# W103X.net
KiCad netlist of a schematic drawn in EAGLE
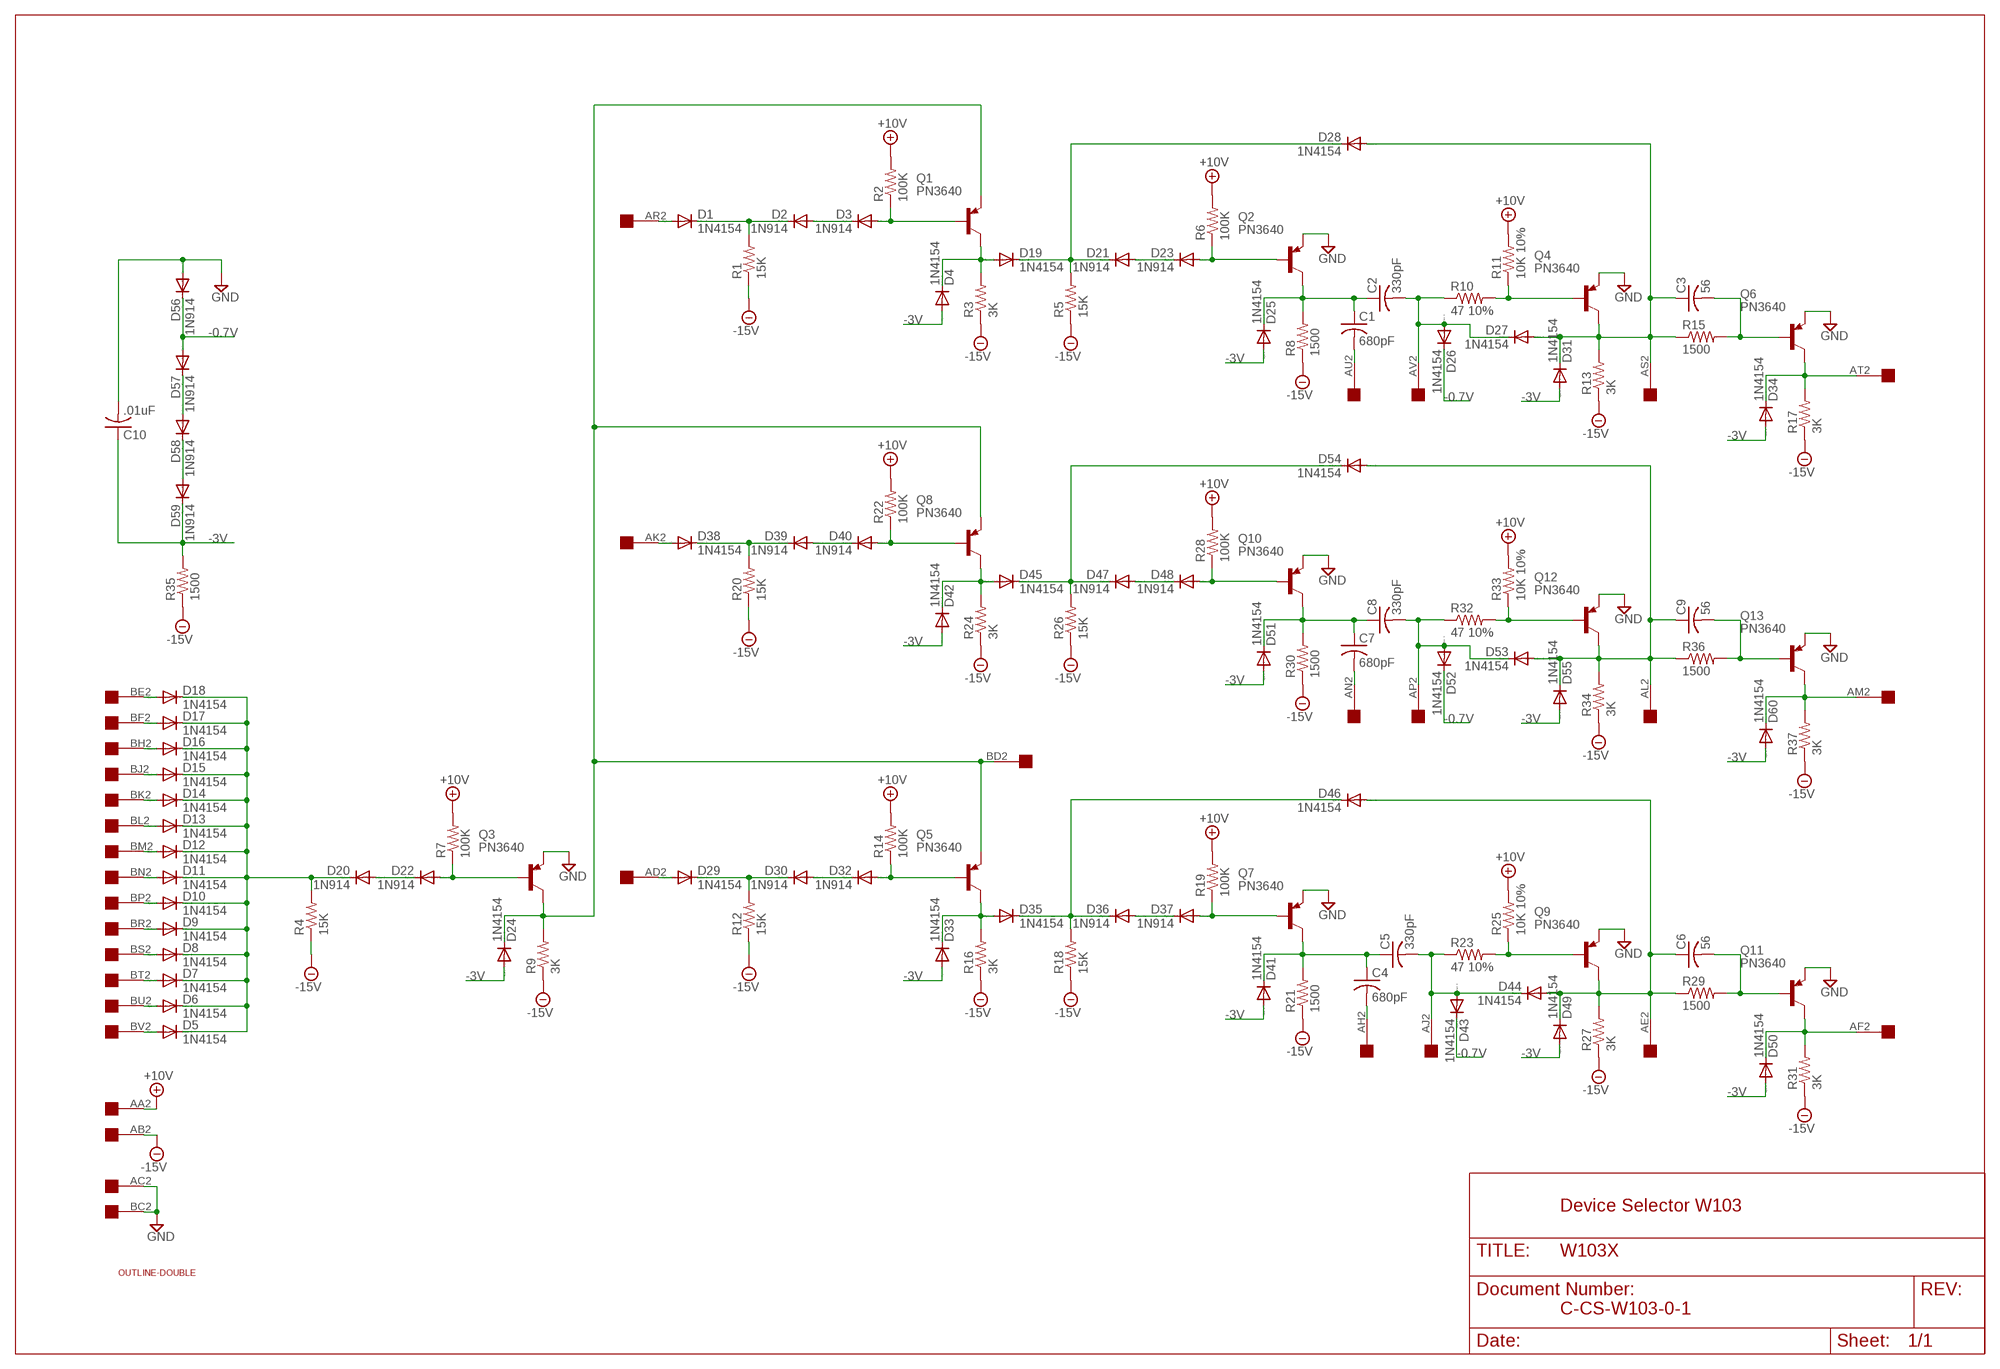
[diagram p0: schematic, sheet 1]

(export (version "E")
  (design (tool "Eeschema 10.0.6"))
  (components
    (comp (ref "C1")
      (value "680pF")
      (footprint "eagle-import:C075-032X103")
      (libsource (lib "eagle-import") (part "C-US075-032X103"))
    )
    (comp (ref "C2")
      (value "330pF")
      (footprint "eagle-import:C075-032X103")
      (libsource (lib "eagle-import") (part "C-US075-032X103"))
    )
    (comp (ref "C3")
      (value "56")
      (footprint "eagle-import:C075-032X103")
      (libsource (lib "eagle-import") (part "C-US075-032X103"))
    )
    (comp (ref "C4")
      (value "680pF")
      (footprint "eagle-import:C075-032X103")
      (libsource (lib "eagle-import") (part "C-US075-032X103"))
    )
    (comp (ref "C5")
      (value "330pF")
      (footprint "eagle-import:C075-032X103")
      (libsource (lib "eagle-import") (part "C-US075-032X103"))
    )
    (comp (ref "C6")
      (value "56")
      (footprint "eagle-import:C075-032X103")
      (libsource (lib "eagle-import") (part "C-US075-032X103"))
    )
    (comp (ref "C7")
      (value "680pF")
      (footprint "eagle-import:C075-032X103")
      (libsource (lib "eagle-import") (part "C-US075-032X103"))
    )
    (comp (ref "C8")
      (value "330pF")
      (footprint "eagle-import:C075-032X103")
      (libsource (lib "eagle-import") (part "C-US075-032X103"))
    )
    (comp (ref "C9")
      (value "56")
      (footprint "eagle-import:C075-032X103")
      (libsource (lib "eagle-import") (part "C-US075-032X103"))
    )
    (comp (ref "C10")
      (value ".01uF")
      (footprint "eagle-import:C075-032X103")
      (libsource (lib "eagle-import") (part "C-US075-032X103"))
    )
    (comp (ref "D1")
      (value "1N4154")
      (footprint "eagle-import:DO35-10")
      (libsource (lib "eagle-import") (part "1N4148DO35-10"))
    )
    (comp (ref "D2")
      (value "1N914")
      (footprint "eagle-import:DO35-10")
      (libsource (lib "eagle-import") (part "1N4148DO35-10"))
    )
    (comp (ref "D3")
      (value "1N914")
      (footprint "eagle-import:DO35-10")
      (libsource (lib "eagle-import") (part "1N4148DO35-10"))
    )
    (comp (ref "D4")
      (value "1N4154")
      (footprint "eagle-import:DO35-10")
      (libsource (lib "eagle-import") (part "1N4148DO35-10"))
    )
    (comp (ref "D5")
      (value "1N4154")
      (footprint "eagle-import:DO35-10")
      (libsource (lib "eagle-import") (part "1N4148DO35-10"))
    )
    (comp (ref "D6")
      (value "1N4154")
      (footprint "eagle-import:DO35-10")
      (libsource (lib "eagle-import") (part "1N4148DO35-10"))
    )
    (comp (ref "D7")
      (value "1N4154")
      (footprint "eagle-import:DO35-10")
      (libsource (lib "eagle-import") (part "1N4148DO35-10"))
    )
    (comp (ref "D8")
      (value "1N4154")
      (footprint "eagle-import:DO35-10")
      (libsource (lib "eagle-import") (part "1N4148DO35-10"))
    )
    (comp (ref "D9")
      (value "1N4154")
      (footprint "eagle-import:DO35-10")
      (libsource (lib "eagle-import") (part "1N4148DO35-10"))
    )
    (comp (ref "D10")
      (value "1N4154")
      (footprint "eagle-import:DO35-10")
      (libsource (lib "eagle-import") (part "1N4148DO35-10"))
    )
    (comp (ref "D11")
      (value "1N4154")
      (footprint "eagle-import:DO35-10")
      (libsource (lib "eagle-import") (part "1N4148DO35-10"))
    )
    (comp (ref "D12")
      (value "1N4154")
      (footprint "eagle-import:DO35-10")
      (libsource (lib "eagle-import") (part "1N4148DO35-10"))
    )
    (comp (ref "D13")
      (value "1N4154")
      (footprint "eagle-import:DO35-10")
      (libsource (lib "eagle-import") (part "1N4148DO35-10"))
    )
    (comp (ref "D14")
      (value "1N4154")
      (footprint "eagle-import:DO35-10")
      (libsource (lib "eagle-import") (part "1N4148DO35-10"))
    )
    (comp (ref "D15")
      (value "1N4154")
      (footprint "eagle-import:DO35-10")
      (libsource (lib "eagle-import") (part "1N4148DO35-10"))
    )
    (comp (ref "D16")
      (value "1N4154")
      (footprint "eagle-import:DO35-10")
      (libsource (lib "eagle-import") (part "1N4148DO35-10"))
    )
    (comp (ref "D17")
      (value "1N4154")
      (footprint "eagle-import:DO35-10")
      (libsource (lib "eagle-import") (part "1N4148DO35-10"))
    )
    (comp (ref "D18")
      (value "1N4154")
      (footprint "eagle-import:DO35-10")
      (libsource (lib "eagle-import") (part "1N4148DO35-10"))
    )
    (comp (ref "D19")
      (value "1N4154")
      (footprint "eagle-import:DO35-10")
      (libsource (lib "eagle-import") (part "1N4148DO35-10"))
    )
    (comp (ref "D20")
      (value "1N914")
      (footprint "eagle-import:DO35-10")
      (libsource (lib "eagle-import") (part "1N4148DO35-10"))
    )
    (comp (ref "D21")
      (value "1N914")
      (footprint "eagle-import:DO35-10")
      (libsource (lib "eagle-import") (part "1N4148DO35-10"))
    )
    (comp (ref "D22")
      (value "1N914")
      (footprint "eagle-import:DO35-10")
      (libsource (lib "eagle-import") (part "1N4148DO35-10"))
    )
    (comp (ref "D23")
      (value "1N914")
      (footprint "eagle-import:DO35-10")
      (libsource (lib "eagle-import") (part "1N4148DO35-10"))
    )
    (comp (ref "D24")
      (value "1N4154")
      (footprint "eagle-import:DO35-10")
      (libsource (lib "eagle-import") (part "1N4148DO35-10"))
    )
    (comp (ref "D25")
      (value "1N4154")
      (footprint "eagle-import:DO35-10")
      (libsource (lib "eagle-import") (part "1N4148DO35-10"))
    )
    (comp (ref "D26")
      (value "1N4154")
      (footprint "eagle-import:DO35-10")
      (libsource (lib "eagle-import") (part "1N4148DO35-10"))
    )
    (comp (ref "D27")
      (value "1N4154")
      (footprint "eagle-import:DO35-10")
      (libsource (lib "eagle-import") (part "1N4148DO35-10"))
    )
    (comp (ref "D28")
      (value "1N4154")
      (footprint "eagle-import:DO35-10")
      (libsource (lib "eagle-import") (part "1N4148DO35-10"))
    )
    (comp (ref "D29")
      (value "1N4154")
      (footprint "eagle-import:DO35-10")
      (libsource (lib "eagle-import") (part "1N4148DO35-10"))
    )
    (comp (ref "D30")
      (value "1N914")
      (footprint "eagle-import:DO35-10")
      (libsource (lib "eagle-import") (part "1N4148DO35-10"))
    )
    (comp (ref "D31")
      (value "1N4154")
      (footprint "eagle-import:DO35-10")
      (libsource (lib "eagle-import") (part "1N4148DO35-10"))
    )
    (comp (ref "D32")
      (value "1N914")
      (footprint "eagle-import:DO35-10")
      (libsource (lib "eagle-import") (part "1N4148DO35-10"))
    )
    (comp (ref "D33")
      (value "1N4154")
      (footprint "eagle-import:DO35-10")
      (libsource (lib "eagle-import") (part "1N4148DO35-10"))
    )
    (comp (ref "D34")
      (value "1N4154")
      (footprint "eagle-import:DO35-10")
      (libsource (lib "eagle-import") (part "1N4148DO35-10"))
    )
    (comp (ref "D35")
      (value "1N4154")
      (footprint "eagle-import:DO35-10")
      (libsource (lib "eagle-import") (part "1N4148DO35-10"))
    )
    (comp (ref "D36")
      (value "1N914")
      (footprint "eagle-import:DO35-10")
      (libsource (lib "eagle-import") (part "1N4148DO35-10"))
    )
    (comp (ref "D37")
      (value "1N914")
      (footprint "eagle-import:DO35-10")
      (libsource (lib "eagle-import") (part "1N4148DO35-10"))
    )
    (comp (ref "D38")
      (value "1N4154")
      (footprint "eagle-import:DO35-10")
      (libsource (lib "eagle-import") (part "1N4148DO35-10"))
    )
    (comp (ref "D39")
      (value "1N914")
      (footprint "eagle-import:DO35-10")
      (libsource (lib "eagle-import") (part "1N4148DO35-10"))
    )
    (comp (ref "D40")
      (value "1N914")
      (footprint "eagle-import:DO35-10")
      (libsource (lib "eagle-import") (part "1N4148DO35-10"))
    )
    (comp (ref "D41")
      (value "1N4154")
      (footprint "eagle-import:DO35-10")
      (libsource (lib "eagle-import") (part "1N4148DO35-10"))
    )
    (comp (ref "D42")
      (value "1N4154")
      (footprint "eagle-import:DO35-10")
      (libsource (lib "eagle-import") (part "1N4148DO35-10"))
    )
    (comp (ref "D43")
      (value "1N4154")
      (footprint "eagle-import:DO35-10")
      (libsource (lib "eagle-import") (part "1N4148DO35-10"))
    )
    (comp (ref "D44")
      (value "1N4154")
      (footprint "eagle-import:DO35-10")
      (libsource (lib "eagle-import") (part "1N4148DO35-10"))
    )
    (comp (ref "D45")
      (value "1N4154")
      (footprint "eagle-import:DO35-10")
      (libsource (lib "eagle-import") (part "1N4148DO35-10"))
    )
    (comp (ref "D46")
      (value "1N4154")
      (footprint "eagle-import:DO35-10")
      (libsource (lib "eagle-import") (part "1N4148DO35-10"))
    )
    (comp (ref "D47")
      (value "1N914")
      (footprint "eagle-import:DO35-10")
      (libsource (lib "eagle-import") (part "1N4148DO35-10"))
    )
    (comp (ref "D48")
      (value "1N914")
      (footprint "eagle-import:DO35-10")
      (libsource (lib "eagle-import") (part "1N4148DO35-10"))
    )
    (comp (ref "D49")
      (value "1N4154")
      (footprint "eagle-import:DO35-10")
      (libsource (lib "eagle-import") (part "1N4148DO35-10"))
    )
    (comp (ref "D50")
      (value "1N4154")
      (footprint "eagle-import:DO35-10")
      (libsource (lib "eagle-import") (part "1N4148DO35-10"))
    )
    (comp (ref "D51")
      (value "1N4154")
      (footprint "eagle-import:DO35-10")
      (libsource (lib "eagle-import") (part "1N4148DO35-10"))
    )
    (comp (ref "D52")
      (value "1N4154")
      (footprint "eagle-import:DO35-10")
      (libsource (lib "eagle-import") (part "1N4148DO35-10"))
    )
    (comp (ref "D53")
      (value "1N4154")
      (footprint "eagle-import:DO35-10")
      (libsource (lib "eagle-import") (part "1N4148DO35-10"))
    )
    (comp (ref "D54")
      (value "1N4154")
      (footprint "eagle-import:DO35-10")
      (libsource (lib "eagle-import") (part "1N4148DO35-10"))
    )
    (comp (ref "D55")
      (value "1N4154")
      (footprint "eagle-import:DO35-10")
      (libsource (lib "eagle-import") (part "1N4148DO35-10"))
    )
    (comp (ref "D56")
      (value "1N914")
      (footprint "eagle-import:DO35-10")
      (libsource (lib "eagle-import") (part "1N4148DO35-10"))
    )
    (comp (ref "D57")
      (value "1N914")
      (footprint "eagle-import:DO35-10")
      (libsource (lib "eagle-import") (part "1N4148DO35-10"))
    )
    (comp (ref "D58")
      (value "1N914")
      (footprint "eagle-import:DO35-10")
      (libsource (lib "eagle-import") (part "1N4148DO35-10"))
    )
    (comp (ref "D59")
      (value "1N914")
      (footprint "eagle-import:DO35-10")
      (libsource (lib "eagle-import") (part "1N4148DO35-10"))
    )
    (comp (ref "D60")
      (value "1N4154")
      (footprint "eagle-import:DO35-10")
      (libsource (lib "eagle-import") (part "1N4148DO35-10"))
    )
    (comp (ref "Q1")
      (value "PN3640")
      (footprint "eagle-import:TO39")
      (libsource (lib "eagle-import") (part "2N2904"))
    )
    (comp (ref "Q2")
      (value "PN3640")
      (footprint "eagle-import:TO39")
      (libsource (lib "eagle-import") (part "2N2904"))
    )
    (comp (ref "Q3")
      (value "PN3640")
      (footprint "eagle-import:TO39")
      (libsource (lib "eagle-import") (part "2N2904"))
    )
    (comp (ref "Q4")
      (value "PN3640")
      (footprint "eagle-import:TO39")
      (libsource (lib "eagle-import") (part "2N2904"))
    )
    (comp (ref "Q5")
      (value "PN3640")
      (footprint "eagle-import:TO39")
      (libsource (lib "eagle-import") (part "2N2904"))
    )
    (comp (ref "Q6")
      (value "PN3640")
      (footprint "eagle-import:TO39")
      (libsource (lib "eagle-import") (part "2N2904"))
    )
    (comp (ref "Q7")
      (value "PN3640")
      (footprint "eagle-import:TO39")
      (libsource (lib "eagle-import") (part "2N2904"))
    )
    (comp (ref "Q8")
      (value "PN3640")
      (footprint "eagle-import:TO39")
      (libsource (lib "eagle-import") (part "2N2904"))
    )
    (comp (ref "Q9")
      (value "PN3640")
      (footprint "eagle-import:TO39")
      (libsource (lib "eagle-import") (part "2N2904"))
    )
    (comp (ref "Q10")
      (value "PN3640")
      (footprint "eagle-import:TO39")
      (libsource (lib "eagle-import") (part "2N2904"))
    )
    (comp (ref "Q11")
      (value "PN3640")
      (footprint "eagle-import:TO39")
      (libsource (lib "eagle-import") (part "2N2904"))
    )
    (comp (ref "Q12")
      (value "PN3640")
      (footprint "eagle-import:TO39")
      (libsource (lib "eagle-import") (part "2N2904"))
    )
    (comp (ref "Q13")
      (value "PN3640")
      (footprint "eagle-import:TO39")
      (libsource (lib "eagle-import") (part "2N2904"))
    )
    (comp (ref "R1")
      (value "15K")
      (footprint "eagle-import:0207_10")
      (libsource (lib "eagle-import") (part "R-US_0207/10"))
    )
    (comp (ref "R2")
      (value "100K")
      (footprint "eagle-import:0207_10")
      (libsource (lib "eagle-import") (part "R-US_0207/10"))
    )
    (comp (ref "R3")
      (value "3K")
      (footprint "eagle-import:0207_10")
      (libsource (lib "eagle-import") (part "R-US_0207/10"))
    )
    (comp (ref "R4")
      (value "15K")
      (footprint "eagle-import:0207_10")
      (libsource (lib "eagle-import") (part "R-US_0207/10"))
    )
    (comp (ref "R5")
      (value "15K")
      (footprint "eagle-import:0207_10")
      (libsource (lib "eagle-import") (part "R-US_0207/10"))
    )
    (comp (ref "R6")
      (value "100K")
      (footprint "eagle-import:0207_10")
      (libsource (lib "eagle-import") (part "R-US_0207/10"))
    )
    (comp (ref "R7")
      (value "100K")
      (footprint "eagle-import:0207_10")
      (libsource (lib "eagle-import") (part "R-US_0207/10"))
    )
    (comp (ref "R8")
      (value "1500")
      (footprint "eagle-import:0207_10")
      (libsource (lib "eagle-import") (part "R-US_0207/10"))
    )
    (comp (ref "R9")
      (value "3K")
      (footprint "eagle-import:0207_10")
      (libsource (lib "eagle-import") (part "R-US_0207/10"))
    )
    (comp (ref "R10")
      (value "47 10%")
      (footprint "eagle-import:0207_10")
      (libsource (lib "eagle-import") (part "R-US_0207/10"))
    )
    (comp (ref "R11")
      (value "10K 10%")
      (footprint "eagle-import:0207_10")
      (libsource (lib "eagle-import") (part "R-US_0207/10"))
    )
    (comp (ref "R12")
      (value "15K")
      (footprint "eagle-import:0207_10")
      (libsource (lib "eagle-import") (part "R-US_0207/10"))
    )
    (comp (ref "R13")
      (value "3K")
      (footprint "eagle-import:0207_10")
      (libsource (lib "eagle-import") (part "R-US_0207/10"))
    )
    (comp (ref "R14")
      (value "100K")
      (footprint "eagle-import:0207_10")
      (libsource (lib "eagle-import") (part "R-US_0207/10"))
    )
    (comp (ref "R15")
      (value "1500")
      (footprint "eagle-import:0207_10")
      (libsource (lib "eagle-import") (part "R-US_0207/10"))
    )
    (comp (ref "R16")
      (value "3K")
      (footprint "eagle-import:0207_10")
      (libsource (lib "eagle-import") (part "R-US_0207/10"))
    )
    (comp (ref "R17")
      (value "3K")
      (footprint "eagle-import:0207_10")
      (libsource (lib "eagle-import") (part "R-US_0207/10"))
    )
    (comp (ref "R18")
      (value "15K")
      (footprint "eagle-import:0207_10")
      (libsource (lib "eagle-import") (part "R-US_0207/10"))
    )
    (comp (ref "R19")
      (value "100K")
      (footprint "eagle-import:0207_10")
      (libsource (lib "eagle-import") (part "R-US_0207/10"))
    )
    (comp (ref "R20")
      (value "15K")
      (footprint "eagle-import:0207_10")
      (libsource (lib "eagle-import") (part "R-US_0207/10"))
    )
    (comp (ref "R21")
      (value "1500")
      (footprint "eagle-import:0207_10")
      (libsource (lib "eagle-import") (part "R-US_0207/10"))
    )
    (comp (ref "R22")
      (value "100K")
      (footprint "eagle-import:0207_10")
      (libsource (lib "eagle-import") (part "R-US_0207/10"))
    )
    (comp (ref "R23")
      (value "47 10%")
      (footprint "eagle-import:0207_10")
      (libsource (lib "eagle-import") (part "R-US_0207/10"))
    )
    (comp (ref "R24")
      (value "3K")
      (footprint "eagle-import:0207_10")
      (libsource (lib "eagle-import") (part "R-US_0207/10"))
    )
    (comp (ref "R25")
      (value "10K 10%")
      (footprint "eagle-import:0207_10")
      (libsource (lib "eagle-import") (part "R-US_0207/10"))
    )
    (comp (ref "R26")
      (value "15K")
      (footprint "eagle-import:0207_10")
      (libsource (lib "eagle-import") (part "R-US_0207/10"))
    )
    (comp (ref "R27")
      (value "3K")
      (footprint "eagle-import:0207_10")
      (libsource (lib "eagle-import") (part "R-US_0207/10"))
    )
    (comp (ref "R28")
      (value "100K")
      (footprint "eagle-import:0207_10")
      (libsource (lib "eagle-import") (part "R-US_0207/10"))
    )
    (comp (ref "R29")
      (value "1500")
      (footprint "eagle-import:0207_10")
      (libsource (lib "eagle-import") (part "R-US_0207/10"))
    )
    (comp (ref "R30")
      (value "1500")
      (footprint "eagle-import:0207_10")
      (libsource (lib "eagle-import") (part "R-US_0207/10"))
    )
    (comp (ref "R31")
      (value "3K")
      (footprint "eagle-import:0207_10")
      (libsource (lib "eagle-import") (part "R-US_0207/10"))
    )
    (comp (ref "R32")
      (value "47 10%")
      (footprint "eagle-import:0207_10")
      (libsource (lib "eagle-import") (part "R-US_0207/10"))
    )
    (comp (ref "R33")
      (value "10K 10%")
      (footprint "eagle-import:0207_10")
      (libsource (lib "eagle-import") (part "R-US_0207/10"))
    )
    (comp (ref "R34")
      (value "3K")
      (footprint "eagle-import:0207_10")
      (libsource (lib "eagle-import") (part "R-US_0207/10"))
    )
    (comp (ref "R35")
      (value "1500")
      (footprint "eagle-import:0207_10")
      (libsource (lib "eagle-import") (part "R-US_0207/10"))
    )
    (comp (ref "R36")
      (value "1500")
      (footprint "eagle-import:0207_10")
      (libsource (lib "eagle-import") (part "R-US_0207/10"))
    )
    (comp (ref "R37")
      (value "3K")
      (footprint "eagle-import:0207_10")
      (libsource (lib "eagle-import") (part "R-US_0207/10"))
    )
    (comp (ref "U$1")
      (value "OUTLINE-DOUBLE")
      (footprint "eagle-import:DOUBLE")
      (libsource (lib "eagle-import") (part "OUTLINE-DOUBLE"))
    )
    (comp (ref "U$2")
      (value "DOUBLE")
      (footprint "eagle-import:EDGE-CON4")
      (libsource (lib "eagle-import") (part "DOUBLE"))
    )
  )
  (nets
    (net (code "1") (name "+10V") (class "Default")
      (node (ref "R11") (pin "2") (pinfunction "2_2") (pintype "passive"))
      (node (ref "R14") (pin "2") (pinfunction "2_2") (pintype "passive"))
      (node (ref "R19") (pin "2") (pinfunction "2_2") (pintype "passive"))
      (node (ref "R2") (pin "2") (pinfunction "2_2") (pintype "passive"))
      (node (ref "R22") (pin "2") (pinfunction "2_2") (pintype "passive"))
      (node (ref "R25") (pin "2") (pinfunction "2_2") (pintype "passive"))
      (node (ref "R28") (pin "2") (pinfunction "2_2") (pintype "passive"))
      (node (ref "R33") (pin "2") (pinfunction "2_2") (pintype "passive"))
      (node (ref "R6") (pin "2") (pinfunction "2_2") (pintype "passive"))
      (node (ref "R7") (pin "2") (pinfunction "2_2") (pintype "passive"))
      (node (ref "U$2") (pin "AA2") (pinfunction "1_AA2") (pintype "bidirectional"))
    )
    (net (code "2") (name "-15V") (class "Default")
      (node (ref "R1") (pin "1") (pinfunction "1_1") (pintype "passive"))
      (node (ref "R12") (pin "1") (pinfunction "1_1") (pintype "passive"))
      (node (ref "R13") (pin "1") (pinfunction "1_1") (pintype "passive"))
      (node (ref "R16") (pin "1") (pinfunction "1_1") (pintype "passive"))
      (node (ref "R17") (pin "1") (pinfunction "1_1") (pintype "passive"))
      (node (ref "R18") (pin "1") (pinfunction "1_1") (pintype "passive"))
      (node (ref "R20") (pin "1") (pinfunction "1_1") (pintype "passive"))
      (node (ref "R21") (pin "1") (pinfunction "1_1") (pintype "passive"))
      (node (ref "R24") (pin "1") (pinfunction "1_1") (pintype "passive"))
      (node (ref "R26") (pin "1") (pinfunction "1_1") (pintype "passive"))
      (node (ref "R27") (pin "1") (pinfunction "1_1") (pintype "passive"))
      (node (ref "R3") (pin "1") (pinfunction "1_1") (pintype "passive"))
      (node (ref "R30") (pin "1") (pinfunction "1_1") (pintype "passive"))
      (node (ref "R31") (pin "1") (pinfunction "1_1") (pintype "passive"))
      (node (ref "R34") (pin "1") (pinfunction "1_1") (pintype "passive"))
      (node (ref "R35") (pin "1") (pinfunction "1_1") (pintype "passive"))
      (node (ref "R37") (pin "1") (pinfunction "1_1") (pintype "passive"))
      (node (ref "R4") (pin "1") (pinfunction "1_1") (pintype "passive"))
      (node (ref "R5") (pin "1") (pinfunction "1_1") (pintype "passive"))
      (node (ref "R8") (pin "1") (pinfunction "1_1") (pintype "passive"))
      (node (ref "R9") (pin "1") (pinfunction "1_1") (pintype "passive"))
      (node (ref "U$2") (pin "AB2") (pinfunction "1_AB2") (pintype "bidirectional"))
    )
    (net (code "3") (name "/-0.7V") (class "Default")
      (node (ref "D26") (pin "C") (pinfunction "C_C") (pintype "passive"))
      (node (ref "D43") (pin "C") (pinfunction "C_C") (pintype "passive"))
      (node (ref "D52") (pin "C") (pinfunction "C_C") (pintype "passive"))
      (node (ref "D56") (pin "C") (pinfunction "C_C") (pintype "passive"))
      (node (ref "D57") (pin "A") (pinfunction "A_A") (pintype "passive"))
    )
    (net (code "4") (name "/-3V") (class "Default")
      (node (ref "C10") (pin "1") (pinfunction "1_1") (pintype "passive"))
      (node (ref "D24") (pin "A") (pinfunction "A_A") (pintype "passive"))
      (node (ref "D25") (pin "A") (pinfunction "A_A") (pintype "passive"))
      (node (ref "D31") (pin "A") (pinfunction "A_A") (pintype "passive"))
      (node (ref "D33") (pin "A") (pinfunction "A_A") (pintype "passive"))
      (node (ref "D34") (pin "A") (pinfunction "A_A") (pintype "passive"))
      (node (ref "D4") (pin "A") (pinfunction "A_A") (pintype "passive"))
      (node (ref "D41") (pin "A") (pinfunction "A_A") (pintype "passive"))
      (node (ref "D42") (pin "A") (pinfunction "A_A") (pintype "passive"))
      (node (ref "D49") (pin "A") (pinfunction "A_A") (pintype "passive"))
      (node (ref "D50") (pin "A") (pinfunction "A_A") (pintype "passive"))
      (node (ref "D51") (pin "A") (pinfunction "A_A") (pintype "passive"))
      (node (ref "D55") (pin "A") (pinfunction "A_A") (pintype "passive"))
      (node (ref "D59") (pin "C") (pinfunction "C_C") (pintype "passive"))
      (node (ref "D60") (pin "A") (pinfunction "A_A") (pintype "passive"))
      (node (ref "R35") (pin "2") (pinfunction "2_2") (pintype "passive"))
    )
    (net (code "5") (name "GND") (class "Default")
      (node (ref "C10") (pin "2") (pinfunction "2_2") (pintype "passive"))
      (node (ref "D56") (pin "A") (pinfunction "A_A") (pintype "passive"))
      (node (ref "Q10") (pin "1") (pinfunction "E_1") (pintype "passive"))
      (node (ref "Q11") (pin "1") (pinfunction "E_1") (pintype "passive"))
      (node (ref "Q12") (pin "1") (pinfunction "E_1") (pintype "passive"))
      (node (ref "Q13") (pin "1") (pinfunction "E_1") (pintype "passive"))
      (node (ref "Q2") (pin "1") (pinfunction "E_1") (pintype "passive"))
      (node (ref "Q3") (pin "1") (pinfunction "E_1") (pintype "passive"))
      (node (ref "Q4") (pin "1") (pinfunction "E_1") (pintype "passive"))
      (node (ref "Q6") (pin "1") (pinfunction "E_1") (pintype "passive"))
      (node (ref "Q7") (pin "1") (pinfunction "E_1") (pintype "passive"))
      (node (ref "Q9") (pin "1") (pinfunction "E_1") (pintype "passive"))
      (node (ref "U$2") (pin "AC2") (pinfunction "1_AC2") (pintype "bidirectional"))
      (node (ref "U$2") (pin "BC2") (pinfunction "1_BC2") (pintype "bidirectional"))
    )
    (net (code "6") (name "Net-(D1-PadC)") (class "Default")
      (node (ref "D1") (pin "C") (pinfunction "C_C") (pintype "passive"))
      (node (ref "D2") (pin "C") (pinfunction "C_C") (pintype "passive"))
      (node (ref "R1") (pin "2") (pinfunction "2_2") (pintype "passive"))
    )
    (net (code "7") (name "Net-(D2-PadA)") (class "Default")
      (node (ref "D2") (pin "A") (pinfunction "A_A") (pintype "passive"))
      (node (ref "D3") (pin "C") (pinfunction "C_C") (pintype "passive"))
    )
    (net (code "8") (name "Net-(D10-PadC)") (class "Default")
      (node (ref "D10") (pin "C") (pinfunction "C_C") (pintype "passive"))
      (node (ref "D11") (pin "C") (pinfunction "C_C") (pintype "passive"))
      (node (ref "D12") (pin "C") (pinfunction "C_C") (pintype "passive"))
      (node (ref "D13") (pin "C") (pinfunction "C_C") (pintype "passive"))
      (node (ref "D14") (pin "C") (pinfunction "C_C") (pintype "passive"))
      (node (ref "D15") (pin "C") (pinfunction "C_C") (pintype "passive"))
      (node (ref "D16") (pin "C") (pinfunction "C_C") (pintype "passive"))
      (node (ref "D17") (pin "C") (pinfunction "C_C") (pintype "passive"))
      (node (ref "D18") (pin "C") (pinfunction "C_C") (pintype "passive"))
      (node (ref "D20") (pin "C") (pinfunction "C_C") (pintype "passive"))
      (node (ref "D5") (pin "C") (pinfunction "C_C") (pintype "passive"))
      (node (ref "D6") (pin "C") (pinfunction "C_C") (pintype "passive"))
      (node (ref "D7") (pin "C") (pinfunction "C_C") (pintype "passive"))
      (node (ref "D8") (pin "C") (pinfunction "C_C") (pintype "passive"))
      (node (ref "D9") (pin "C") (pinfunction "C_C") (pintype "passive"))
      (node (ref "R4") (pin "2") (pinfunction "2_2") (pintype "passive"))
    )
    (net (code "9") (name "Net-(D19-PadC)") (class "Default")
      (node (ref "D19") (pin "C") (pinfunction "C_C") (pintype "passive"))
      (node (ref "D21") (pin "C") (pinfunction "C_C") (pintype "passive"))
      (node (ref "D28") (pin "C") (pinfunction "C_C") (pintype "passive"))
      (node (ref "R5") (pin "2") (pinfunction "2_2") (pintype "passive"))
    )
    (net (code "10") (name "Net-(D20-PadA)") (class "Default")
      (node (ref "D20") (pin "A") (pinfunction "A_A") (pintype "passive"))
      (node (ref "D22") (pin "C") (pinfunction "C_C") (pintype "passive"))
    )
    (net (code "11") (name "Net-(D21-PadA)") (class "Default")
      (node (ref "D21") (pin "A") (pinfunction "A_A") (pintype "passive"))
      (node (ref "D23") (pin "C") (pinfunction "C_C") (pintype "passive"))
    )
    (net (code "12") (name "Net-(D29-PadC)") (class "Default")
      (node (ref "D29") (pin "C") (pinfunction "C_C") (pintype "passive"))
      (node (ref "D30") (pin "C") (pinfunction "C_C") (pintype "passive"))
      (node (ref "R12") (pin "2") (pinfunction "2_2") (pintype "passive"))
    )
    (net (code "13") (name "Net-(D30-PadA)") (class "Default")
      (node (ref "D30") (pin "A") (pinfunction "A_A") (pintype "passive"))
      (node (ref "D32") (pin "C") (pinfunction "C_C") (pintype "passive"))
    )
    (net (code "14") (name "Net-(D35-PadC)") (class "Default")
      (node (ref "D35") (pin "C") (pinfunction "C_C") (pintype "passive"))
      (node (ref "D36") (pin "C") (pinfunction "C_C") (pintype "passive"))
      (node (ref "D46") (pin "C") (pinfunction "C_C") (pintype "passive"))
      (node (ref "R18") (pin "2") (pinfunction "2_2") (pintype "passive"))
    )
    (net (code "15") (name "Net-(D36-PadA)") (class "Default")
      (node (ref "D36") (pin "A") (pinfunction "A_A") (pintype "passive"))
      (node (ref "D37") (pin "C") (pinfunction "C_C") (pintype "passive"))
    )
    (net (code "16") (name "Net-(D38-PadC)") (class "Default")
      (node (ref "D38") (pin "C") (pinfunction "C_C") (pintype "passive"))
      (node (ref "D39") (pin "C") (pinfunction "C_C") (pintype "passive"))
      (node (ref "R20") (pin "2") (pinfunction "2_2") (pintype "passive"))
    )
    (net (code "17") (name "Net-(D39-PadA)") (class "Default")
      (node (ref "D39") (pin "A") (pinfunction "A_A") (pintype "passive"))
      (node (ref "D40") (pin "C") (pinfunction "C_C") (pintype "passive"))
    )
    (net (code "18") (name "Net-(D45-PadC)") (class "Default")
      (node (ref "D45") (pin "C") (pinfunction "C_C") (pintype "passive"))
      (node (ref "D47") (pin "C") (pinfunction "C_C") (pintype "passive"))
      (node (ref "D54") (pin "C") (pinfunction "C_C") (pintype "passive"))
      (node (ref "R26") (pin "2") (pinfunction "2_2") (pintype "passive"))
    )
    (net (code "19") (name "Net-(D47-PadA)") (class "Default")
      (node (ref "D47") (pin "A") (pinfunction "A_A") (pintype "passive"))
      (node (ref "D48") (pin "C") (pinfunction "C_C") (pintype "passive"))
    )
    (net (code "20") (name "Net-(D57-PadC)") (class "Default")
      (node (ref "D57") (pin "C") (pinfunction "C_C") (pintype "passive"))
      (node (ref "D58") (pin "A") (pinfunction "A_A") (pintype "passive"))
    )
    (net (code "21") (name "Net-(D58-PadC)") (class "Default")
      (node (ref "D58") (pin "C") (pinfunction "C_C") (pintype "passive"))
      (node (ref "D59") (pin "A") (pinfunction "A_A") (pintype "passive"))
    )
    (net (code "22") (name "Net-(Q1-B)") (class "Default")
      (node (ref "D3") (pin "A") (pinfunction "A_A") (pintype "passive"))
      (node (ref "Q1") (pin "2") (pinfunction "B_2") (pintype "passive"))
      (node (ref "R2") (pin "1") (pinfunction "1_1") (pintype "passive"))
    )
    (net (code "23") (name "Net-(Q1-C)") (class "Default")
      (node (ref "D19") (pin "A") (pinfunction "A_A") (pintype "passive"))
      (node (ref "D4") (pin "C") (pinfunction "C_C") (pintype "passive"))
      (node (ref "Q1") (pin "3") (pinfunction "C_3") (pintype "passive"))
      (node (ref "R3") (pin "2") (pinfunction "2_2") (pintype "passive"))
    )
    (net (code "24") (name "Net-(Q1-E)") (class "Default")
      (node (ref "D24") (pin "C") (pinfunction "C_C") (pintype "passive"))
      (node (ref "Q1") (pin "1") (pinfunction "E_1") (pintype "passive"))
      (node (ref "Q3") (pin "3") (pinfunction "C_3") (pintype "passive"))
      (node (ref "Q5") (pin "1") (pinfunction "E_1") (pintype "passive"))
      (node (ref "Q8") (pin "1") (pinfunction "E_1") (pintype "passive"))
      (node (ref "R9") (pin "2") (pinfunction "2_2") (pintype "passive"))
      (node (ref "U$2") (pin "BD2") (pinfunction "1_BD2") (pintype "bidirectional"))
    )
    (net (code "25") (name "Net-(Q2-B)") (class "Default")
      (node (ref "D23") (pin "A") (pinfunction "A_A") (pintype "passive"))
      (node (ref "Q2") (pin "2") (pinfunction "B_2") (pintype "passive"))
      (node (ref "R6") (pin "1") (pinfunction "1_1") (pintype "passive"))
    )
    (net (code "26") (name "Net-(Q2-C)") (class "Default")
      (node (ref "C1") (pin "1") (pinfunction "1_1") (pintype "passive"))
      (node (ref "C2") (pin "1") (pinfunction "1_1") (pintype "passive"))
      (node (ref "D25") (pin "C") (pinfunction "C_C") (pintype "passive"))
      (node (ref "Q2") (pin "3") (pinfunction "C_3") (pintype "passive"))
      (node (ref "R8") (pin "2") (pinfunction "2_2") (pintype "passive"))
    )
    (net (code "27") (name "Net-(Q3-B)") (class "Default")
      (node (ref "D22") (pin "A") (pinfunction "A_A") (pintype "passive"))
      (node (ref "Q3") (pin "2") (pinfunction "B_2") (pintype "passive"))
      (node (ref "R7") (pin "1") (pinfunction "1_1") (pintype "passive"))
    )
    (net (code "28") (name "Net-(Q4-B)") (class "Default")
      (node (ref "Q4") (pin "2") (pinfunction "B_2") (pintype "passive"))
      (node (ref "R10") (pin "2") (pinfunction "2_2") (pintype "passive"))
      (node (ref "R11") (pin "1") (pinfunction "1_1") (pintype "passive"))
    )
    (net (code "29") (name "Net-(Q4-C)") (class "Default")
      (node (ref "C3") (pin "1") (pinfunction "1_1") (pintype "passive"))
      (node (ref "D27") (pin "A") (pinfunction "A_A") (pintype "passive"))
      (node (ref "D28") (pin "A") (pinfunction "A_A") (pintype "passive"))
      (node (ref "D31") (pin "C") (pinfunction "C_C") (pintype "passive"))
      (node (ref "Q4") (pin "3") (pinfunction "C_3") (pintype "passive"))
      (node (ref "R13") (pin "2") (pinfunction "2_2") (pintype "passive"))
      (node (ref "R15") (pin "1") (pinfunction "1_1") (pintype "passive"))
      (node (ref "U$2") (pin "AS2") (pinfunction "1_AS2") (pintype "bidirectional"))
    )
    (net (code "30") (name "Net-(Q5-B)") (class "Default")
      (node (ref "D32") (pin "A") (pinfunction "A_A") (pintype "passive"))
      (node (ref "Q5") (pin "2") (pinfunction "B_2") (pintype "passive"))
      (node (ref "R14") (pin "1") (pinfunction "1_1") (pintype "passive"))
    )
    (net (code "31") (name "Net-(Q5-C)") (class "Default")
      (node (ref "D33") (pin "C") (pinfunction "C_C") (pintype "passive"))
      (node (ref "D35") (pin "A") (pinfunction "A_A") (pintype "passive"))
      (node (ref "Q5") (pin "3") (pinfunction "C_3") (pintype "passive"))
      (node (ref "R16") (pin "2") (pinfunction "2_2") (pintype "passive"))
    )
    (net (code "32") (name "Net-(Q6-B)") (class "Default")
      (node (ref "C3") (pin "2") (pinfunction "2_2") (pintype "passive"))
      (node (ref "Q6") (pin "2") (pinfunction "B_2") (pintype "passive"))
      (node (ref "R15") (pin "2") (pinfunction "2_2") (pintype "passive"))
    )
    (net (code "33") (name "Net-(Q6-C)") (class "Default")
      (node (ref "D34") (pin "C") (pinfunction "C_C") (pintype "passive"))
      (node (ref "Q6") (pin "3") (pinfunction "C_3") (pintype "passive"))
      (node (ref "R17") (pin "2") (pinfunction "2_2") (pintype "passive"))
      (node (ref "U$2") (pin "AT2") (pinfunction "1_AT2") (pintype "bidirectional"))
    )
    (net (code "34") (name "Net-(Q7-B)") (class "Default")
      (node (ref "D37") (pin "A") (pinfunction "A_A") (pintype "passive"))
      (node (ref "Q7") (pin "2") (pinfunction "B_2") (pintype "passive"))
      (node (ref "R19") (pin "1") (pinfunction "1_1") (pintype "passive"))
    )
    (net (code "35") (name "Net-(Q7-C)") (class "Default")
      (node (ref "C4") (pin "1") (pinfunction "1_1") (pintype "passive"))
      (node (ref "C5") (pin "1") (pinfunction "1_1") (pintype "passive"))
      (node (ref "D41") (pin "C") (pinfunction "C_C") (pintype "passive"))
      (node (ref "Q7") (pin "3") (pinfunction "C_3") (pintype "passive"))
      (node (ref "R21") (pin "2") (pinfunction "2_2") (pintype "passive"))
    )
    (net (code "36") (name "Net-(Q8-B)") (class "Default")
      (node (ref "D40") (pin "A") (pinfunction "A_A") (pintype "passive"))
      (node (ref "Q8") (pin "2") (pinfunction "B_2") (pintype "passive"))
      (node (ref "R22") (pin "1") (pinfunction "1_1") (pintype "passive"))
    )
    (net (code "37") (name "Net-(Q8-C)") (class "Default")
      (node (ref "D42") (pin "C") (pinfunction "C_C") (pintype "passive"))
      (node (ref "D45") (pin "A") (pinfunction "A_A") (pintype "passive"))
      (node (ref "Q8") (pin "3") (pinfunction "C_3") (pintype "passive"))
      (node (ref "R24") (pin "2") (pinfunction "2_2") (pintype "passive"))
    )
    (net (code "38") (name "Net-(Q9-B)") (class "Default")
      (node (ref "Q9") (pin "2") (pinfunction "B_2") (pintype "passive"))
      (node (ref "R23") (pin "2") (pinfunction "2_2") (pintype "passive"))
      (node (ref "R25") (pin "1") (pinfunction "1_1") (pintype "passive"))
    )
    (net (code "39") (name "Net-(Q9-C)") (class "Default")
      (node (ref "C6") (pin "1") (pinfunction "1_1") (pintype "passive"))
      (node (ref "D44") (pin "A") (pinfunction "A_A") (pintype "passive"))
      (node (ref "D46") (pin "A") (pinfunction "A_A") (pintype "passive"))
      (node (ref "D49") (pin "C") (pinfunction "C_C") (pintype "passive"))
      (node (ref "Q9") (pin "3") (pinfunction "C_3") (pintype "passive"))
      (node (ref "R27") (pin "2") (pinfunction "2_2") (pintype "passive"))
      (node (ref "R29") (pin "1") (pinfunction "1_1") (pintype "passive"))
      (node (ref "U$2") (pin "AE2") (pinfunction "1_AE2") (pintype "bidirectional"))
    )
    (net (code "40") (name "Net-(Q10-B)") (class "Default")
      (node (ref "D48") (pin "A") (pinfunction "A_A") (pintype "passive"))
      (node (ref "Q10") (pin "2") (pinfunction "B_2") (pintype "passive"))
      (node (ref "R28") (pin "1") (pinfunction "1_1") (pintype "passive"))
    )
    (net (code "41") (name "Net-(Q10-C)") (class "Default")
      (node (ref "C7") (pin "1") (pinfunction "1_1") (pintype "passive"))
      (node (ref "C8") (pin "1") (pinfunction "1_1") (pintype "passive"))
      (node (ref "D51") (pin "C") (pinfunction "C_C") (pintype "passive"))
      (node (ref "Q10") (pin "3") (pinfunction "C_3") (pintype "passive"))
      (node (ref "R30") (pin "2") (pinfunction "2_2") (pintype "passive"))
    )
    (net (code "42") (name "Net-(Q11-B)") (class "Default")
      (node (ref "C6") (pin "2") (pinfunction "2_2") (pintype "passive"))
      (node (ref "Q11") (pin "2") (pinfunction "B_2") (pintype "passive"))
      (node (ref "R29") (pin "2") (pinfunction "2_2") (pintype "passive"))
    )
    (net (code "43") (name "Net-(Q11-C)") (class "Default")
      (node (ref "D50") (pin "C") (pinfunction "C_C") (pintype "passive"))
      (node (ref "Q11") (pin "3") (pinfunction "C_3") (pintype "passive"))
      (node (ref "R31") (pin "2") (pinfunction "2_2") (pintype "passive"))
      (node (ref "U$2") (pin "AF2") (pinfunction "1_AF2") (pintype "bidirectional"))
    )
    (net (code "44") (name "Net-(Q12-B)") (class "Default")
      (node (ref "Q12") (pin "2") (pinfunction "B_2") (pintype "passive"))
      (node (ref "R32") (pin "2") (pinfunction "2_2") (pintype "passive"))
      (node (ref "R33") (pin "1") (pinfunction "1_1") (pintype "passive"))
    )
    (net (code "45") (name "Net-(Q12-C)") (class "Default")
      (node (ref "C9") (pin "1") (pinfunction "1_1") (pintype "passive"))
      (node (ref "D53") (pin "A") (pinfunction "A_A") (pintype "passive"))
      (node (ref "D54") (pin "A") (pinfunction "A_A") (pintype "passive"))
      (node (ref "D55") (pin "C") (pinfunction "C_C") (pintype "passive"))
      (node (ref "Q12") (pin "3") (pinfunction "C_3") (pintype "passive"))
      (node (ref "R34") (pin "2") (pinfunction "2_2") (pintype "passive"))
      (node (ref "R36") (pin "1") (pinfunction "1_1") (pintype "passive"))
      (node (ref "U$2") (pin "AL2") (pinfunction "1_AL2") (pintype "bidirectional"))
    )
    (net (code "46") (name "Net-(Q13-B)") (class "Default")
      (node (ref "C9") (pin "2") (pinfunction "2_2") (pintype "passive"))
      (node (ref "Q13") (pin "2") (pinfunction "B_2") (pintype "passive"))
      (node (ref "R36") (pin "2") (pinfunction "2_2") (pintype "passive"))
    )
    (net (code "47") (name "Net-(Q13-C)") (class "Default")
      (node (ref "D60") (pin "C") (pinfunction "C_C") (pintype "passive"))
      (node (ref "Q13") (pin "3") (pinfunction "C_3") (pintype "passive"))
      (node (ref "R37") (pin "2") (pinfunction "2_2") (pintype "passive"))
      (node (ref "U$2") (pin "AM2") (pinfunction "1_AM2") (pintype "bidirectional"))
    )
    (net (code "48") (name "Net-(U$2AB-1)") (class "Default")
      (node (ref "D1") (pin "A") (pinfunction "A_A") (pintype "passive"))
      (node (ref "U$2") (pin "AR2") (pinfunction "1_AR2") (pintype "bidirectional"))
    )
    (net (code "49") (name "Net-(U$2AH-1)") (class "Default")
      (node (ref "C1") (pin "2") (pinfunction "2_2") (pintype "passive"))
      (node (ref "U$2") (pin "AU2") (pinfunction "1_AU2") (pintype "bidirectional"))
    )
    (net (code "50") (name "Net-(U$2AJ-1)") (class "Default")
      (node (ref "C2") (pin "2") (pinfunction "2_2") (pintype "passive"))
      (node (ref "D26") (pin "A") (pinfunction "A_A") (pintype "passive"))
      (node (ref "D27") (pin "C") (pinfunction "C_C") (pintype "passive"))
      (node (ref "R10") (pin "1") (pinfunction "1_1") (pintype "passive"))
      (node (ref "U$2") (pin "AV2") (pinfunction "1_AV2") (pintype "bidirectional"))
    )
    (net (code "51") (name "Net-(U$2AT-1)") (class "Default")
      (node (ref "D18") (pin "A") (pinfunction "A_A") (pintype "passive"))
      (node (ref "U$2") (pin "BE2") (pinfunction "1_BE2") (pintype "bidirectional"))
    )
    (net (code "52") (name "Net-(U$2AV-1)") (class "Default")
      (node (ref "D17") (pin "A") (pinfunction "A_A") (pintype "passive"))
      (node (ref "U$2") (pin "BF2") (pinfunction "1_BF2") (pintype "bidirectional"))
    )
    (net (code "53") (name "Net-(U$2AX-1)") (class "Default")
      (node (ref "D16") (pin "A") (pinfunction "A_A") (pintype "passive"))
      (node (ref "U$2") (pin "BH2") (pinfunction "1_BH2") (pintype "bidirectional"))
    )
    (net (code "54") (name "Net-(U$2AZ-1)") (class "Default")
      (node (ref "D15") (pin "A") (pinfunction "A_A") (pintype "passive"))
      (node (ref "U$2") (pin "BJ2") (pinfunction "1_BJ2") (pintype "bidirectional"))
    )
    (net (code "55") (name "Net-(U$2BB-1)") (class "Default")
      (node (ref "D14") (pin "A") (pinfunction "A_A") (pintype "passive"))
      (node (ref "U$2") (pin "BK2") (pinfunction "1_BK2") (pintype "bidirectional"))
    )
    (net (code "56") (name "Net-(U$2BD-1)") (class "Default")
      (node (ref "D13") (pin "A") (pinfunction "A_A") (pintype "passive"))
      (node (ref "U$2") (pin "BL2") (pinfunction "1_BL2") (pintype "bidirectional"))
    )
    (net (code "57") (name "Net-(U$2BF-1)") (class "Default")
      (node (ref "D12") (pin "A") (pinfunction "A_A") (pintype "passive"))
      (node (ref "U$2") (pin "BM2") (pinfunction "1_BM2") (pintype "bidirectional"))
    )
    (net (code "58") (name "Net-(U$2BH-1)") (class "Default")
      (node (ref "D11") (pin "A") (pinfunction "A_A") (pintype "passive"))
      (node (ref "U$2") (pin "BN2") (pinfunction "1_BN2") (pintype "bidirectional"))
    )
    (net (code "59") (name "Net-(U$2BJ-1)") (class "Default")
      (node (ref "D10") (pin "A") (pinfunction "A_A") (pintype "passive"))
      (node (ref "U$2") (pin "BP2") (pinfunction "1_BP2") (pintype "bidirectional"))
    )
    (net (code "60") (name "Net-(U$2BL-1)") (class "Default")
      (node (ref "D9") (pin "A") (pinfunction "A_A") (pintype "passive"))
      (node (ref "U$2") (pin "BR2") (pinfunction "1_BR2") (pintype "bidirectional"))
    )
    (net (code "61") (name "Net-(U$2BN-1)") (class "Default")
      (node (ref "D8") (pin "A") (pinfunction "A_A") (pintype "passive"))
      (node (ref "U$2") (pin "BS2") (pinfunction "1_BS2") (pintype "bidirectional"))
    )
    (net (code "62") (name "Net-(U$2BP-1)") (class "Default")
      (node (ref "D7") (pin "A") (pinfunction "A_A") (pintype "passive"))
      (node (ref "U$2") (pin "BT2") (pinfunction "1_BT2") (pintype "bidirectional"))
    )
    (net (code "63") (name "Net-(U$2BR-1)") (class "Default")
      (node (ref "D6") (pin "A") (pinfunction "A_A") (pintype "passive"))
      (node (ref "U$2") (pin "BU2") (pinfunction "1_BU2") (pintype "bidirectional"))
    )
    (net (code "64") (name "Net-(U$2BT-1)") (class "Default")
      (node (ref "D5") (pin "A") (pinfunction "A_A") (pintype "passive"))
      (node (ref "U$2") (pin "BV2") (pinfunction "1_BV2") (pintype "bidirectional"))
    )
    (net (code "65") (name "Net-(U$2H-1)") (class "Default")
      (node (ref "D29") (pin "A") (pinfunction "A_A") (pintype "passive"))
      (node (ref "U$2") (pin "AD2") (pinfunction "1_AD2") (pintype "bidirectional"))
    )
    (net (code "66") (name "Net-(U$2N-1)") (class "Default")
      (node (ref "C4") (pin "2") (pinfunction "2_2") (pintype "passive"))
      (node (ref "U$2") (pin "AH2") (pinfunction "1_AH2") (pintype "bidirectional"))
    )
    (net (code "67") (name "Net-(U$2P-1)") (class "Default")
      (node (ref "C5") (pin "2") (pinfunction "2_2") (pintype "passive"))
      (node (ref "D43") (pin "A") (pinfunction "A_A") (pintype "passive"))
      (node (ref "D44") (pin "C") (pinfunction "C_C") (pintype "passive"))
      (node (ref "R23") (pin "1") (pinfunction "1_1") (pintype "passive"))
      (node (ref "U$2") (pin "AJ2") (pinfunction "1_AJ2") (pintype "bidirectional"))
    )
    (net (code "68") (name "Net-(U$2R-1)") (class "Default")
      (node (ref "D38") (pin "A") (pinfunction "A_A") (pintype "passive"))
      (node (ref "U$2") (pin "AK2") (pinfunction "1_AK2") (pintype "bidirectional"))
    )
    (net (code "69") (name "Net-(U$2X-1)") (class "Default")
      (node (ref "C7") (pin "2") (pinfunction "2_2") (pintype "passive"))
      (node (ref "U$2") (pin "AN2") (pinfunction "1_AN2") (pintype "bidirectional"))
    )
    (net (code "70") (name "Net-(U$2Z-1)") (class "Default")
      (node (ref "C8") (pin "2") (pinfunction "2_2") (pintype "passive"))
      (node (ref "D52") (pin "A") (pinfunction "A_A") (pintype "passive"))
      (node (ref "D53") (pin "C") (pinfunction "C_C") (pintype "passive"))
      (node (ref "R32") (pin "1") (pinfunction "1_1") (pintype "passive"))
      (node (ref "U$2") (pin "AP2") (pinfunction "1_AP2") (pintype "bidirectional"))
    )
  )
)
